# alcd.net
KiCad netlist of a schematic drawn in Altium Designer
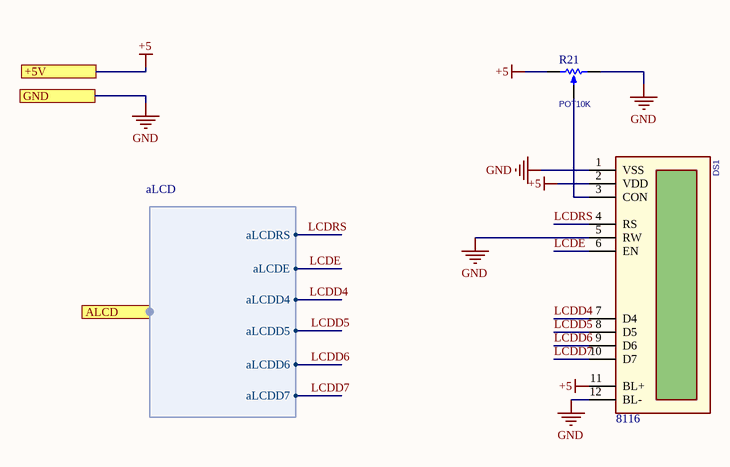
[diagram p0: alcd.SchDoc]

(export (version "E")
  (design (tool "Eeschema 10.0.6"))
  (components
    (comp (ref "DS1")
      (value "16x2")
      (footprint "BOX-HDR-2x6-2.54mm-S")
      (description "Alphanumeric LCD character")
      (fields (field (name "INFLOW") "8116") (field (name "VALIDATION") "Valid"))
      (libsource (lib "aKaReZa") (part "ModSen_LCD_CH_16x2_Box"))
    )
    (comp (ref "R21")
      (value "POT10K")
      (footprint "POT_3296W")
      (description "RESISTOR, THD, Potentiometer Multiturn, most Popular")
      (libsource (lib "Chila_PCB") (part "RES_THD_POT_MULTITURN"))
    )
  )
  (nets
    (net (code "2") (name "+5") (class "Default")
      (node (ref "DS1") (pin "11") (pinfunction "BL+_11") (pintype "passive"))
      (node (ref "DS1") (pin "2") (pinfunction "VDD_2") (pintype "passive"))
      (node (ref "R21") (pin "1") (pinfunction "TOP_1") (pintype "passive"))
    )
    (net (code "3") (name "/LCDD4") (class "Default")
      (node (ref "DS1") (pin "7") (pinfunction "D4_7") (pintype "passive"))
    )
    (net (code "4") (name "/LCDD5") (class "Default")
      (node (ref "DS1") (pin "8") (pinfunction "D5_8") (pintype "passive"))
    )
    (net (code "5") (name "/LCDD6") (class "Default")
      (node (ref "DS1") (pin "9") (pinfunction "D6_9") (pintype "passive"))
    )
    (net (code "6") (name "/LCDD7") (class "Default")
      (node (ref "DS1") (pin "10") (pinfunction "D7_10") (pintype "passive"))
    )
    (net (code "7") (name "/LCDE") (class "Default")
      (node (ref "DS1") (pin "6") (pinfunction "EN_6") (pintype "passive"))
    )
    (net (code "8") (name "/LCDRS") (class "Default")
      (node (ref "DS1") (pin "4") (pinfunction "RS_4") (pintype "passive"))
    )
    (net (code "10") (name "GND") (class "Default")
      (node (ref "DS1") (pin "1") (pinfunction "VSS_1") (pintype "passive"))
      (node (ref "DS1") (pin "12") (pinfunction "BL-_12") (pintype "passive"))
      (node (ref "DS1") (pin "5") (pinfunction "RW_5") (pintype "passive"))
      (node (ref "R21") (pin "3") (pinfunction "BOT_3") (pintype "passive"))
    )
    (net (code "11") (name "Net-(DS1-CON)") (class "Default")
      (node (ref "DS1") (pin "3") (pinfunction "CON_3") (pintype "passive"))
      (node (ref "R21") (pin "2") (pinfunction "TAP_2") (pintype "passive"))
    )
  )
)
